# NET.net
KiCad netlist of a schematic drawn in Altium Designer
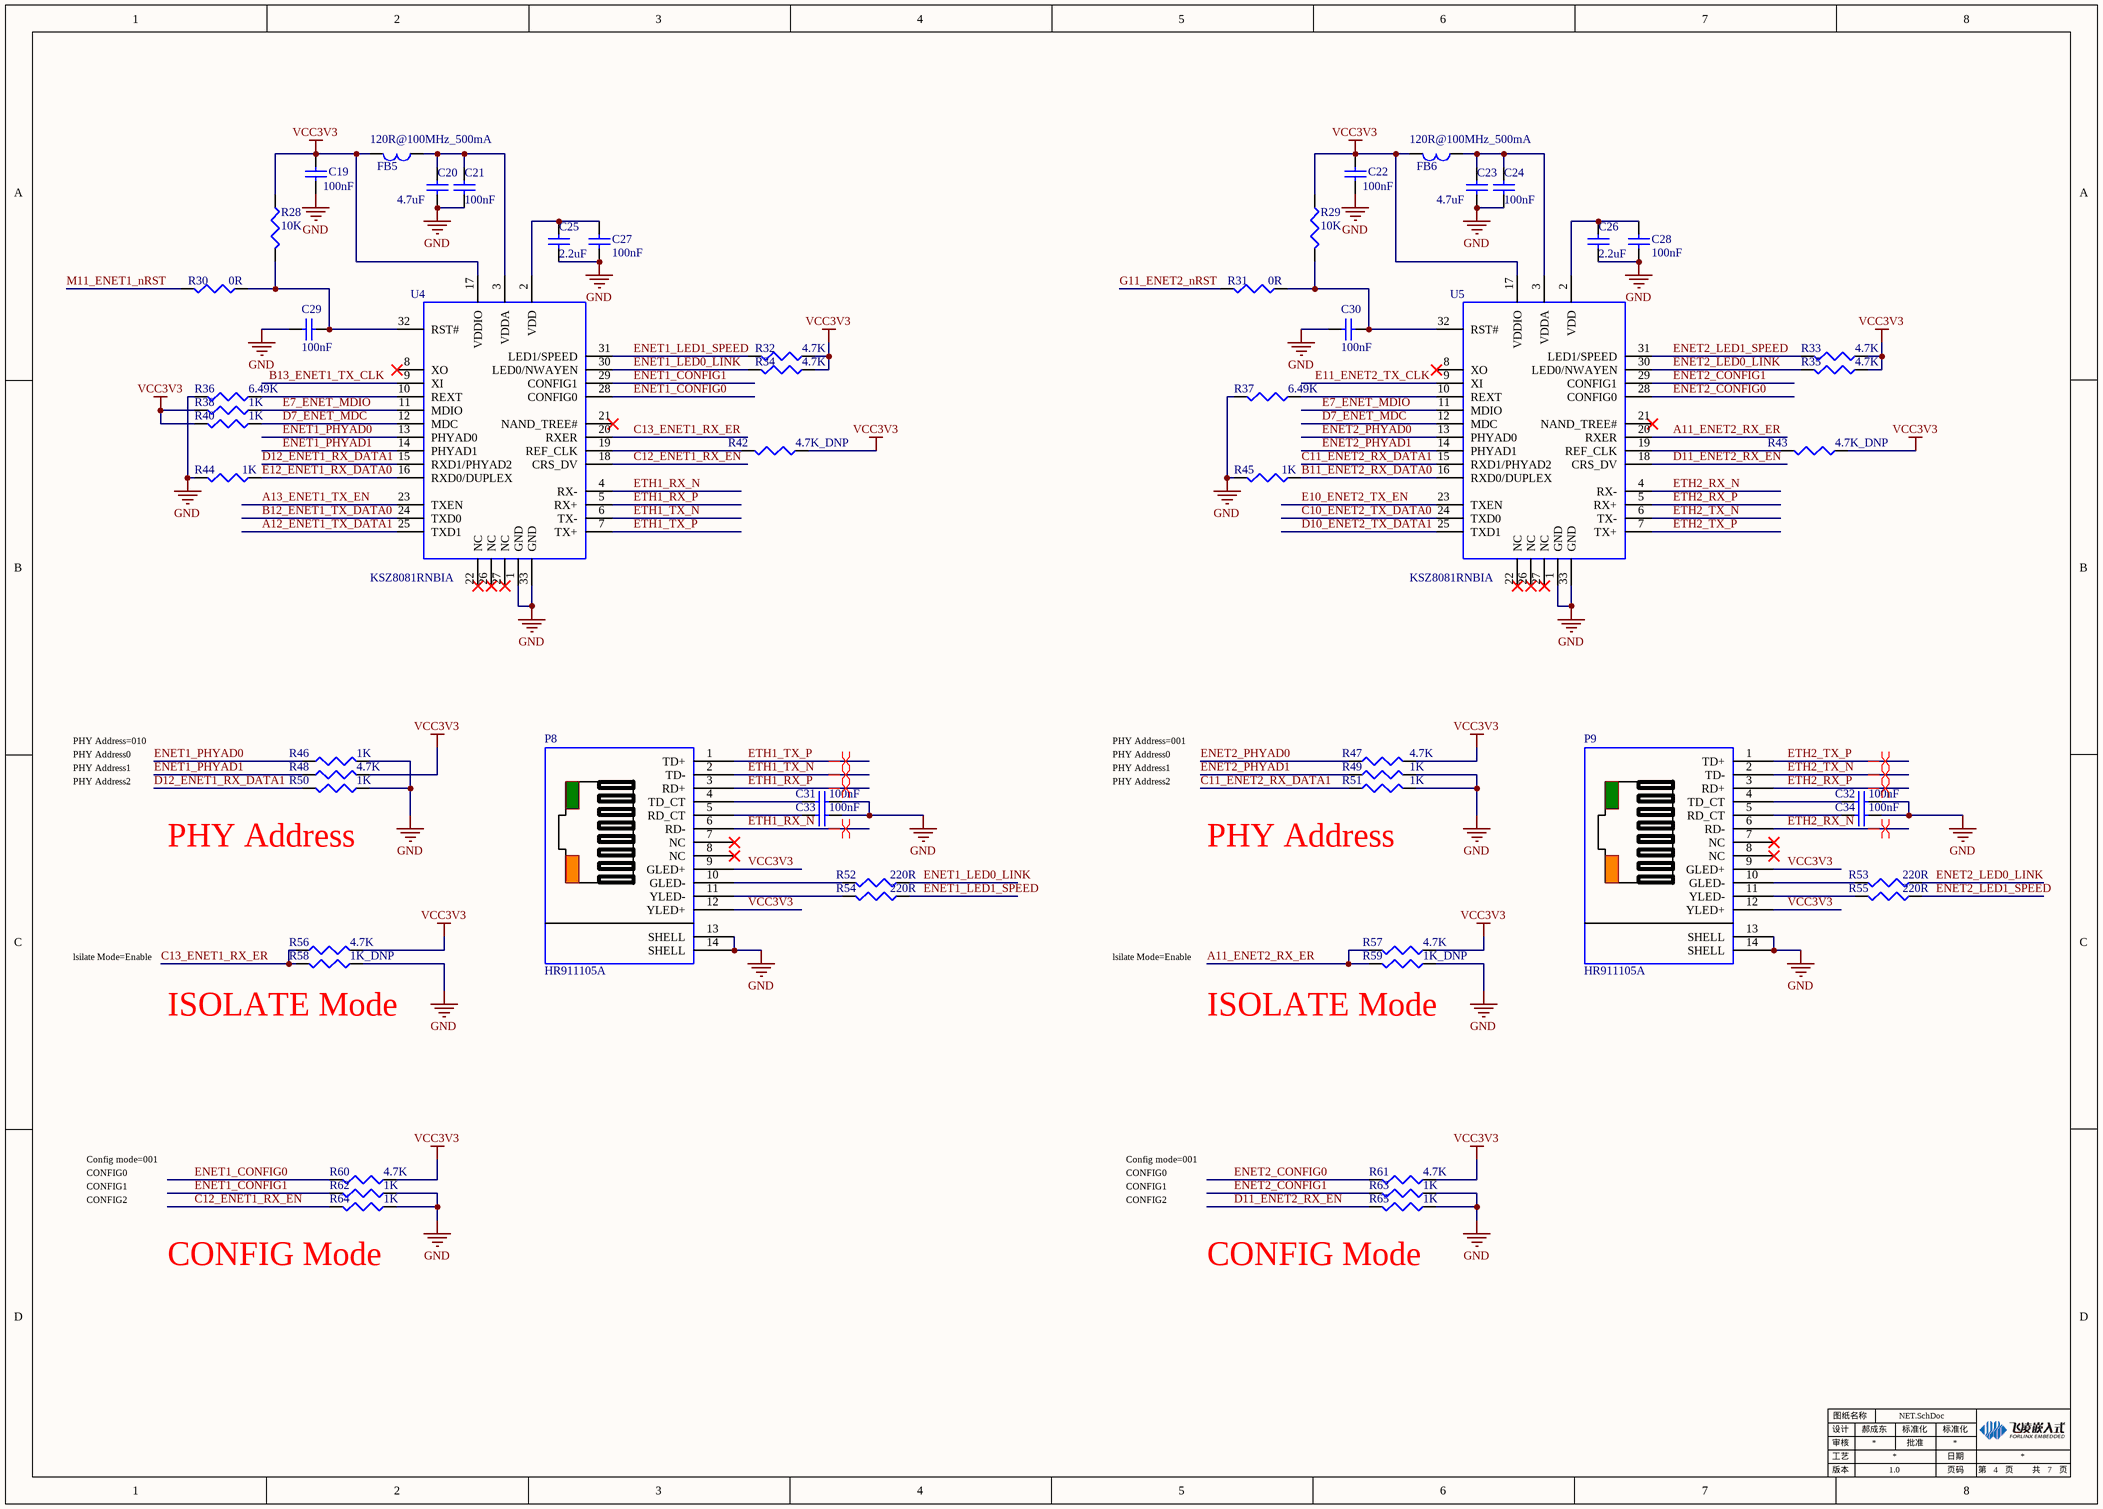
[diagram p0: NET.SchDoc]

(export (version "E")
  (design (tool "Eeschema 10.0.6"))
  (components
    (comp (ref "C19")
      (value "100nF")
      (footprint "0603C+")
      (description "Capacitor")
      (fields (field (name "PUBLISHER") "Altium Limited"))
      (libsource (lib "Miscellaneous Devices") (part "Cap"))
    )
    (comp (ref "C20")
      (value "4.7uF")
      (footprint "0603C+")
      (description "Capacitor")
      (fields (field (name "PUBLISHER") "Altium Limited"))
      (libsource (lib "Miscellaneous Devices") (part "Cap"))
    )
    (comp (ref "C21")
      (value "100nF")
      (footprint "0603C+")
      (description "Capacitor")
      (fields (field (name "PUBLISHER") "Altium Limited"))
      (libsource (lib "Miscellaneous Devices") (part "Cap"))
    )
    (comp (ref "C22")
      (value "100nF")
      (footprint "0603C+")
      (description "Capacitor")
      (fields (field (name "PUBLISHER") "Altium Limited"))
      (libsource (lib "Miscellaneous Devices") (part "Cap"))
    )
    (comp (ref "C23")
      (value "4.7uF")
      (footprint "0603C+")
      (description "Capacitor")
      (fields (field (name "PUBLISHER") "Altium Limited"))
      (libsource (lib "Miscellaneous Devices") (part "Cap"))
    )
    (comp (ref "C24")
      (value "100nF")
      (footprint "0603C+")
      (description "Capacitor")
      (fields (field (name "PUBLISHER") "Altium Limited"))
      (libsource (lib "Miscellaneous Devices") (part "Cap"))
    )
    (comp (ref "C25")
      (value "2.2uF")
      (footprint "0603C+")
      (description "Capacitor")
      (fields (field (name "PUBLISHER") "Altium Limited"))
      (libsource (lib "Miscellaneous Devices") (part "Cap"))
    )
    (comp (ref "C26")
      (value "2.2uF")
      (footprint "0603C+")
      (description "Capacitor")
      (fields (field (name "PUBLISHER") "Altium Limited"))
      (libsource (lib "Miscellaneous Devices") (part "Cap"))
    )
    (comp (ref "C27")
      (value "100nF")
      (footprint "0603C+")
      (description "Capacitor")
      (fields (field (name "PUBLISHER") "Altium Limited"))
      (libsource (lib "Miscellaneous Devices") (part "Cap"))
    )
    (comp (ref "C28")
      (value "100nF")
      (footprint "0603C+")
      (description "Capacitor")
      (fields (field (name "PUBLISHER") "Altium Limited"))
      (libsource (lib "Miscellaneous Devices") (part "Cap"))
    )
    (comp (ref "C29")
      (value "100nF")
      (footprint "0603C+")
      (description "Capacitor")
      (fields (field (name "PUBLISHER") "Altium Limited"))
      (libsource (lib "Miscellaneous Devices") (part "Cap"))
    )
    (comp (ref "C30")
      (value "100nF")
      (footprint "0603C+")
      (description "Capacitor")
      (fields (field (name "PUBLISHER") "Altium Limited"))
      (libsource (lib "Miscellaneous Devices") (part "Cap"))
    )
    (comp (ref "C31")
      (value "100nF")
      (footprint "0603C+")
      (description "Capacitor")
      (fields (field (name "PUBLISHER") "Altium Limited"))
      (libsource (lib "Miscellaneous Devices") (part "Cap"))
    )
    (comp (ref "C32")
      (value "100nF")
      (footprint "0603C+")
      (description "Capacitor")
      (fields (field (name "PUBLISHER") "Altium Limited"))
      (libsource (lib "Miscellaneous Devices") (part "Cap"))
    )
    (comp (ref "C33")
      (value "100nF")
      (footprint "0603C+")
      (description "Capacitor")
      (fields (field (name "PUBLISHER") "Altium Limited"))
      (libsource (lib "Miscellaneous Devices") (part "Cap"))
    )
    (comp (ref "C34")
      (value "100nF")
      (footprint "0603C+")
      (description "Capacitor")
      (fields (field (name "PUBLISHER") "Altium Limited"))
      (libsource (lib "Miscellaneous Devices") (part "Cap"))
    )
    (comp (ref "FB5")
      (value "120R@100MHz_500mA")
      (footprint "0603R+")
      (description "Inductor")
      (fields (field (name "PUBLISHER") "120R@100MHz_500mA"))
      (libsource (lib "Schlib_UL") (part "CZ"))
    )
    (comp (ref "FB6")
      (value "120R@100MHz_500mA")
      (footprint "0603R+")
      (description "Inductor")
      (fields (field (name "PUBLISHER") "120R@100MHz_500mA"))
      (libsource (lib "Schlib_UL") (part "CZ"))
    )
    (comp (ref "P8")
      (value "HR911105A")
      (footprint "RJ-45A12")
      (libsource (lib "PCB_RT1052") (part "HR911105A"))
    )
    (comp (ref "P9")
      (value "HR911105A")
      (footprint "RJ-45A12")
      (libsource (lib "PCB_RT1052") (part "HR911105A"))
    )
    (comp (ref "R28")
      (value "10K")
      (footprint "0603R+")
      (description "Resistor")
      (fields (field (name "PUBLISHER") "Altium Limited"))
      (libsource (lib "Miscellaneous Devices") (part "Res3"))
    )
    (comp (ref "R29")
      (value "10K")
      (footprint "0603R+")
      (description "Resistor")
      (fields (field (name "PUBLISHER") "Altium Limited"))
      (libsource (lib "Miscellaneous Devices") (part "Res3"))
    )
    (comp (ref "R30")
      (value "0R")
      (footprint "0603R+")
      (description "Resistor")
      (fields (field (name "PUBLISHER") "Altium Limited"))
      (libsource (lib "Miscellaneous Devices") (part "Res3"))
    )
    (comp (ref "R31")
      (value "0R")
      (footprint "0603R+")
      (description "Resistor")
      (fields (field (name "PUBLISHER") "Altium Limited"))
      (libsource (lib "Miscellaneous Devices") (part "Res3"))
    )
    (comp (ref "R32")
      (value "4.7K")
      (footprint "0603R+")
      (description "Resistor")
      (fields (field (name "PUBLISHER") "Altium Limited"))
      (libsource (lib "Miscellaneous Devices") (part "Res3"))
    )
    (comp (ref "R33")
      (value "4.7K")
      (footprint "0603R+")
      (description "Resistor")
      (fields (field (name "PUBLISHER") "Altium Limited"))
      (libsource (lib "Miscellaneous Devices") (part "Res3"))
    )
    (comp (ref "R34")
      (value "4.7K")
      (footprint "0603R+")
      (description "Resistor")
      (fields (field (name "PUBLISHER") "Altium Limited"))
      (libsource (lib "Miscellaneous Devices") (part "Res3"))
    )
    (comp (ref "R35")
      (value "4.7K")
      (footprint "0603R+")
      (description "Resistor")
      (fields (field (name "PUBLISHER") "Altium Limited"))
      (libsource (lib "Miscellaneous Devices") (part "Res3"))
    )
    (comp (ref "R36")
      (value "6.49K")
      (footprint "0603R+")
      (description "Resistor")
      (fields (field (name "PUBLISHER") "Altium Limited"))
      (libsource (lib "Miscellaneous Devices") (part "Res3"))
    )
    (comp (ref "R37")
      (value "6.49K")
      (footprint "0603R+")
      (description "Resistor")
      (fields (field (name "PUBLISHER") "Altium Limited"))
      (libsource (lib "Miscellaneous Devices") (part "Res3"))
    )
    (comp (ref "R38")
      (value "1K")
      (footprint "0603R+")
      (description "Resistor")
      (fields (field (name "PUBLISHER") "Altium Limited"))
      (libsource (lib "Miscellaneous Devices") (part "Res3"))
    )
    (comp (ref "R40")
      (value "1K")
      (footprint "0603R+")
      (description "Resistor")
      (fields (field (name "PUBLISHER") "Altium Limited"))
      (libsource (lib "Miscellaneous Devices") (part "Res3"))
    )
    (comp (ref "R42")
      (value "4.7K_DNP")
      (footprint "0603R+")
      (description "Resistor")
      (fields (field (name "PUBLISHER") "Altium Limited"))
      (libsource (lib "Miscellaneous Devices") (part "Res3"))
    )
    (comp (ref "R43")
      (value "4.7K_DNP")
      (footprint "0603R+")
      (description "Resistor")
      (fields (field (name "PUBLISHER") "Altium Limited"))
      (libsource (lib "Miscellaneous Devices") (part "Res3"))
    )
    (comp (ref "R44")
      (value "1K")
      (footprint "0603R+")
      (description "Resistor")
      (fields (field (name "PUBLISHER") "Altium Limited"))
      (libsource (lib "Miscellaneous Devices") (part "Res3"))
    )
    (comp (ref "R45")
      (value "1K")
      (footprint "0603R+")
      (description "Resistor")
      (fields (field (name "PUBLISHER") "Altium Limited"))
      (libsource (lib "Miscellaneous Devices") (part "Res3"))
    )
    (comp (ref "R46")
      (value "1K")
      (footprint "0603R+")
      (description "Resistor")
      (fields (field (name "PUBLISHER") "Altium Limited"))
      (libsource (lib "Miscellaneous Devices") (part "Res3"))
    )
    (comp (ref "R47")
      (value "4.7K")
      (footprint "0603R+")
      (description "Resistor")
      (fields (field (name "PUBLISHER") "Altium Limited"))
      (libsource (lib "Miscellaneous Devices") (part "Res3"))
    )
    (comp (ref "R48")
      (value "4.7K")
      (footprint "0603R+")
      (description "Resistor")
      (fields (field (name "PUBLISHER") "Altium Limited"))
      (libsource (lib "Miscellaneous Devices") (part "Res3"))
    )
    (comp (ref "R49")
      (value "1K")
      (footprint "0603R+")
      (description "Resistor")
      (fields (field (name "PUBLISHER") "Altium Limited"))
      (libsource (lib "Miscellaneous Devices") (part "Res3"))
    )
    (comp (ref "R50")
      (value "1K")
      (footprint "0603R+")
      (description "Resistor")
      (fields (field (name "PUBLISHER") "Altium Limited"))
      (libsource (lib "Miscellaneous Devices") (part "Res3"))
    )
    (comp (ref "R51")
      (value "1K")
      (footprint "0603R+")
      (description "Resistor")
      (fields (field (name "PUBLISHER") "Altium Limited"))
      (libsource (lib "Miscellaneous Devices") (part "Res3"))
    )
    (comp (ref "R52")
      (value "220R")
      (footprint "0603R+")
      (description "Resistor")
      (fields (field (name "PUBLISHER") "Altium Limited"))
      (libsource (lib "Miscellaneous Devices") (part "Res3"))
    )
    (comp (ref "R53")
      (value "220R")
      (footprint "0603R+")
      (description "Resistor")
      (fields (field (name "PUBLISHER") "Altium Limited"))
      (libsource (lib "Miscellaneous Devices") (part "Res3"))
    )
    (comp (ref "R54")
      (value "220R")
      (footprint "0603R+")
      (description "Resistor")
      (fields (field (name "PUBLISHER") "Altium Limited"))
      (libsource (lib "Miscellaneous Devices") (part "Res3"))
    )
    (comp (ref "R55")
      (value "220R")
      (footprint "0603R+")
      (description "Resistor")
      (fields (field (name "PUBLISHER") "Altium Limited"))
      (libsource (lib "Miscellaneous Devices") (part "Res3"))
    )
    (comp (ref "R56")
      (value "4.7K")
      (footprint "0603R+")
      (description "Resistor")
      (fields (field (name "PUBLISHER") "Altium Limited"))
      (libsource (lib "Miscellaneous Devices") (part "Res3"))
    )
    (comp (ref "R57")
      (value "4.7K")
      (footprint "0603R+")
      (description "Resistor")
      (fields (field (name "PUBLISHER") "Altium Limited"))
      (libsource (lib "Miscellaneous Devices") (part "Res3"))
    )
    (comp (ref "R58")
      (value "1K_DNP")
      (footprint "0603R+")
      (description "Resistor")
      (fields (field (name "PUBLISHER") "Altium Limited"))
      (libsource (lib "Miscellaneous Devices") (part "Res3"))
    )
    (comp (ref "R59")
      (value "1K_DNP")
      (footprint "0603R+")
      (description "Resistor")
      (fields (field (name "PUBLISHER") "Altium Limited"))
      (libsource (lib "Miscellaneous Devices") (part "Res3"))
    )
    (comp (ref "R60")
      (value "4.7K")
      (footprint "0603R+")
      (description "Resistor")
      (fields (field (name "PUBLISHER") "Altium Limited"))
      (libsource (lib "Miscellaneous Devices") (part "Res3"))
    )
    (comp (ref "R61")
      (value "4.7K")
      (footprint "0603R+")
      (description "Resistor")
      (fields (field (name "PUBLISHER") "Altium Limited"))
      (libsource (lib "Miscellaneous Devices") (part "Res3"))
    )
    (comp (ref "R62")
      (value "1K")
      (footprint "0603R+")
      (description "Resistor")
      (fields (field (name "PUBLISHER") "Altium Limited"))
      (libsource (lib "Miscellaneous Devices") (part "Res3"))
    )
    (comp (ref "R63")
      (value "1K")
      (footprint "0603R+")
      (description "Resistor")
      (fields (field (name "PUBLISHER") "Altium Limited"))
      (libsource (lib "Miscellaneous Devices") (part "Res3"))
    )
    (comp (ref "R64")
      (value "1K")
      (footprint "0603R+")
      (description "Resistor")
      (fields (field (name "PUBLISHER") "Altium Limited"))
      (libsource (lib "Miscellaneous Devices") (part "Res3"))
    )
    (comp (ref "R65")
      (value "1K")
      (footprint "0603R+")
      (description "Resistor")
      (fields (field (name "PUBLISHER") "Altium Limited"))
      (libsource (lib "Miscellaneous Devices") (part "Res3"))
    )
    (comp (ref "U4")
      (value "KSZ8081RNBIA")
      (footprint "QFN-32")
      (libsource (lib "PCB_RT1052") (part "KSZ8081RNB"))
    )
    (comp (ref "U5")
      (value "KSZ8081RNBIA")
      (footprint "QFN-32")
      (libsource (lib "PCB_RT1052") (part "KSZ8081RNB"))
    )
  )
  (nets
    (net (code "1") (name "/A11_ENET2_RX_ER") (class "Default")
      (node (ref "R57") (pin "2") (pinfunction "2_2") (pintype "passive"))
      (node (ref "R59") (pin "2") (pinfunction "2_2") (pintype "passive"))
      (node (ref "U5") (pin "20") (pinfunction "RXER_20") (pintype "passive"))
    )
    (net (code "2") (name "/A12_ENET1_TX_DATA1") (class "Default")
      (node (ref "U4") (pin "25") (pinfunction "TXD1_25") (pintype "passive"))
    )
    (net (code "3") (name "/A13_ENET1_TX_EN") (class "Default")
      (node (ref "U4") (pin "23") (pinfunction "TXEN_23") (pintype "passive"))
    )
    (net (code "4") (name "/B11_ENET2_RX_DATA0") (class "Default")
      (node (ref "R45") (pin "1") (pinfunction "1_1") (pintype "passive"))
      (node (ref "U5") (pin "16") (pinfunction "RXD0/DUPLEX_16") (pintype "passive"))
    )
    (net (code "5") (name "/B12_ENET1_TX_DATA0") (class "Default")
      (node (ref "U4") (pin "24") (pinfunction "TXD0_24") (pintype "passive"))
    )
    (net (code "6") (name "/B13_ENET1_TX_CLK") (class "Default")
      (node (ref "U4") (pin "9") (pinfunction "XI_9") (pintype "passive"))
    )
    (net (code "7") (name "/C10_ENET2_TX_DATA0") (class "Default")
      (node (ref "U5") (pin "24") (pinfunction "TXD0_24") (pintype "passive"))
    )
    (net (code "8") (name "/C11_ENET2_RX_DATA1") (class "Default")
      (node (ref "R51") (pin "1") (pinfunction "1_1") (pintype "passive"))
      (node (ref "U5") (pin "15") (pinfunction "RXD1/PHYAD2_15") (pintype "passive"))
    )
    (net (code "9") (name "/C12_ENET1_RX_EN") (class "Default")
      (node (ref "R64") (pin "2") (pinfunction "2_2") (pintype "passive"))
      (node (ref "U4") (pin "18") (pinfunction "CRS_DV_18") (pintype "passive"))
    )
    (net (code "10") (name "/C13_ENET1_RX_ER") (class "Default")
      (node (ref "R56") (pin "1") (pinfunction "1_1") (pintype "passive"))
      (node (ref "R58") (pin "2") (pinfunction "2_2") (pintype "passive"))
      (node (ref "U4") (pin "20") (pinfunction "RXER_20") (pintype "passive"))
    )
    (net (code "11") (name "/D7_ENET_MDC") (class "Default")
      (node (ref "R40") (pin "1") (pinfunction "1_1") (pintype "passive"))
      (node (ref "U4") (pin "12") (pinfunction "MDC_12") (pintype "passive"))
      (node (ref "U5") (pin "12") (pinfunction "MDC_12") (pintype "passive"))
    )
    (net (code "12") (name "/D10_ENET2_TX_DATA1") (class "Default")
      (node (ref "U5") (pin "25") (pinfunction "TXD1_25") (pintype "passive"))
    )
    (net (code "13") (name "/D11_ENET2_RX_EN") (class "Default")
      (node (ref "R65") (pin "2") (pinfunction "2_2") (pintype "passive"))
      (node (ref "U5") (pin "18") (pinfunction "CRS_DV_18") (pintype "passive"))
    )
    (net (code "14") (name "/D12_ENET1_RX_DATA1") (class "Default")
      (node (ref "R50") (pin "2") (pinfunction "2_2") (pintype "passive"))
      (node (ref "U4") (pin "15") (pinfunction "RXD1/PHYAD2_15") (pintype "passive"))
    )
    (net (code "15") (name "/E7_ENET_MDIO") (class "Default")
      (node (ref "R38") (pin "1") (pinfunction "1_1") (pintype "passive"))
      (node (ref "U4") (pin "11") (pinfunction "MDIO_11") (pintype "passive"))
      (node (ref "U5") (pin "11") (pinfunction "MDIO_11") (pintype "passive"))
    )
    (net (code "16") (name "/E10_ENET2_TX_EN") (class "Default")
      (node (ref "U5") (pin "23") (pinfunction "TXEN_23") (pintype "passive"))
    )
    (net (code "17") (name "/E11_ENET2_TX_CLK") (class "Default")
      (node (ref "U5") (pin "9") (pinfunction "XI_9") (pintype "passive"))
    )
    (net (code "18") (name "/E12_ENET1_RX_DATA0") (class "Default")
      (node (ref "R44") (pin "1") (pinfunction "1_1") (pintype "passive"))
      (node (ref "U4") (pin "16") (pinfunction "RXD0/DUPLEX_16") (pintype "passive"))
    )
    (net (code "19") (name "/ENET1_CONFIG0") (class "Default")
      (node (ref "R60") (pin "2") (pinfunction "2_2") (pintype "passive"))
      (node (ref "U4") (pin "28") (pinfunction "CONFIG0_28") (pintype "passive"))
    )
    (net (code "20") (name "/ENET1_CONFIG1") (class "Default")
      (node (ref "R62") (pin "2") (pinfunction "2_2") (pintype "passive"))
      (node (ref "U4") (pin "29") (pinfunction "CONFIG1_29") (pintype "passive"))
    )
    (net (code "21") (name "/ENET1_LED0_LINK") (class "Default")
      (node (ref "R34") (pin "2") (pinfunction "2_2") (pintype "passive"))
      (node (ref "R52") (pin "1") (pinfunction "1_1") (pintype "passive"))
      (node (ref "U4") (pin "30") (pinfunction "LED0/NWAYEN_30") (pintype "passive"))
    )
    (net (code "22") (name "/ENET1_LED1_SPEED") (class "Default")
      (node (ref "R32") (pin "2") (pinfunction "2_2") (pintype "passive"))
      (node (ref "R54") (pin "1") (pinfunction "1_1") (pintype "passive"))
      (node (ref "U4") (pin "31") (pinfunction "LED1/SPEED_31") (pintype "passive"))
    )
    (net (code "23") (name "/ENET1_PHYAD0") (class "Default")
      (node (ref "R46") (pin "1") (pinfunction "1_1") (pintype "passive"))
      (node (ref "U4") (pin "13") (pinfunction "PHYAD0_13") (pintype "passive"))
    )
    (net (code "24") (name "/ENET1_PHYAD1") (class "Default")
      (node (ref "R48") (pin "1") (pinfunction "1_1") (pintype "passive"))
      (node (ref "U4") (pin "14") (pinfunction "PHYAD1_14") (pintype "passive"))
    )
    (net (code "25") (name "/ENET2_CONFIG0") (class "Default")
      (node (ref "R61") (pin "2") (pinfunction "2_2") (pintype "passive"))
      (node (ref "U5") (pin "28") (pinfunction "CONFIG0_28") (pintype "passive"))
    )
    (net (code "26") (name "/ENET2_CONFIG1") (class "Default")
      (node (ref "R63") (pin "2") (pinfunction "2_2") (pintype "passive"))
      (node (ref "U5") (pin "29") (pinfunction "CONFIG1_29") (pintype "passive"))
    )
    (net (code "27") (name "/ENET2_LED0_LINK") (class "Default")
      (node (ref "R35") (pin "2") (pinfunction "2_2") (pintype "passive"))
      (node (ref "R53") (pin "1") (pinfunction "1_1") (pintype "passive"))
      (node (ref "U5") (pin "30") (pinfunction "LED0/NWAYEN_30") (pintype "passive"))
    )
    (net (code "28") (name "/ENET2_LED1_SPEED") (class "Default")
      (node (ref "R33") (pin "2") (pinfunction "2_2") (pintype "passive"))
      (node (ref "R55") (pin "1") (pinfunction "1_1") (pintype "passive"))
      (node (ref "U5") (pin "31") (pinfunction "LED1/SPEED_31") (pintype "passive"))
    )
    (net (code "29") (name "/ENET2_PHYAD0") (class "Default")
      (node (ref "R47") (pin "1") (pinfunction "1_1") (pintype "passive"))
      (node (ref "U5") (pin "13") (pinfunction "PHYAD0_13") (pintype "passive"))
    )
    (net (code "30") (name "/ENET2_PHYAD1") (class "Default")
      (node (ref "R49") (pin "1") (pinfunction "1_1") (pintype "passive"))
      (node (ref "U5") (pin "14") (pinfunction "PHYAD1_14") (pintype "passive"))
    )
    (net (code "31") (name "/ETH1_RX_N") (class "Default")
      (node (ref "P8") (pin "6") (pinfunction "RD-_6") (pintype "passive"))
      (node (ref "U4") (pin "4") (pinfunction "RX-_4") (pintype "passive"))
    )
    (net (code "32") (name "/ETH1_RX_P") (class "Default")
      (node (ref "P8") (pin "3") (pinfunction "RD+_3") (pintype "passive"))
      (node (ref "U4") (pin "5") (pinfunction "RX+_5") (pintype "passive"))
    )
    (net (code "33") (name "/ETH1_TX_N") (class "Default")
      (node (ref "P8") (pin "2") (pinfunction "TD-_2") (pintype "passive"))
      (node (ref "U4") (pin "6") (pinfunction "TX-_6") (pintype "passive"))
    )
    (net (code "34") (name "/ETH1_TX_P") (class "Default")
      (node (ref "P8") (pin "1") (pinfunction "TD+_1") (pintype "passive"))
      (node (ref "U4") (pin "7") (pinfunction "TX+_7") (pintype "passive"))
    )
    (net (code "35") (name "/ETH2_RX_N") (class "Default")
      (node (ref "P9") (pin "6") (pinfunction "RD-_6") (pintype "passive"))
      (node (ref "U5") (pin "4") (pinfunction "RX-_4") (pintype "passive"))
    )
    (net (code "36") (name "/ETH2_RX_P") (class "Default")
      (node (ref "P9") (pin "3") (pinfunction "RD+_3") (pintype "passive"))
      (node (ref "U5") (pin "5") (pinfunction "RX+_5") (pintype "passive"))
    )
    (net (code "37") (name "/ETH2_TX_N") (class "Default")
      (node (ref "P9") (pin "2") (pinfunction "TD-_2") (pintype "passive"))
      (node (ref "U5") (pin "6") (pinfunction "TX-_6") (pintype "passive"))
    )
    (net (code "38") (name "/ETH2_TX_P") (class "Default")
      (node (ref "P9") (pin "1") (pinfunction "TD+_1") (pintype "passive"))
      (node (ref "U5") (pin "7") (pinfunction "TX+_7") (pintype "passive"))
    )
    (net (code "39") (name "/G11_ENET2_nRST") (class "Default")
      (node (ref "R31") (pin "2") (pinfunction "2_2") (pintype "passive"))
    )
    (net (code "40") (name "/M11_ENET1_nRST") (class "Default")
      (node (ref "R30") (pin "2") (pinfunction "2_2") (pintype "passive"))
    )
    (net (code "41") (name "GND") (class "Default")
      (node (ref "C19") (pin "2") (pinfunction "2_2") (pintype "passive"))
      (node (ref "C20") (pin "2") (pinfunction "2_2") (pintype "passive"))
      (node (ref "C21") (pin "2") (pinfunction "2_2") (pintype "passive"))
      (node (ref "C22") (pin "2") (pinfunction "2_2") (pintype "passive"))
      (node (ref "C23") (pin "2") (pinfunction "2_2") (pintype "passive"))
      (node (ref "C24") (pin "2") (pinfunction "2_2") (pintype "passive"))
      (node (ref "C25") (pin "2") (pinfunction "2_2") (pintype "passive"))
      (node (ref "C26") (pin "2") (pinfunction "2_2") (pintype "passive"))
      (node (ref "C27") (pin "2") (pinfunction "2_2") (pintype "passive"))
      (node (ref "C28") (pin "2") (pinfunction "2_2") (pintype "passive"))
      (node (ref "C29") (pin "1") (pinfunction "1_1") (pintype "passive"))
      (node (ref "C30") (pin "1") (pinfunction "1_1") (pintype "passive"))
      (node (ref "C31") (pin "1") (pinfunction "1_1") (pintype "passive"))
      (node (ref "C32") (pin "1") (pinfunction "1_1") (pintype "passive"))
      (node (ref "C33") (pin "1") (pinfunction "1_1") (pintype "passive"))
      (node (ref "C34") (pin "1") (pinfunction "1_1") (pintype "passive"))
      (node (ref "P8") (pin "13") (pinfunction "SHELL_13") (pintype "passive"))
      (node (ref "P8") (pin "14") (pinfunction "SHELL_14") (pintype "passive"))
      (node (ref "P9") (pin "13") (pinfunction "SHELL_13") (pintype "passive"))
      (node (ref "P9") (pin "14") (pinfunction "SHELL_14") (pintype "passive"))
      (node (ref "R36") (pin "2") (pinfunction "2_2") (pintype "passive"))
      (node (ref "R37") (pin "2") (pinfunction "2_2") (pintype "passive"))
      (node (ref "R44") (pin "2") (pinfunction "2_2") (pintype "passive"))
      (node (ref "R45") (pin "2") (pinfunction "2_2") (pintype "passive"))
      (node (ref "R46") (pin "2") (pinfunction "2_2") (pintype "passive"))
      (node (ref "R49") (pin "2") (pinfunction "2_2") (pintype "passive"))
      (node (ref "R50") (pin "1") (pinfunction "1_1") (pintype "passive"))
      (node (ref "R51") (pin "2") (pinfunction "2_2") (pintype "passive"))
      (node (ref "R58") (pin "1") (pinfunction "1_1") (pintype "passive"))
      (node (ref "R59") (pin "1") (pinfunction "1_1") (pintype "passive"))
      (node (ref "R62") (pin "1") (pinfunction "1_1") (pintype "passive"))
      (node (ref "R63") (pin "1") (pinfunction "1_1") (pintype "passive"))
      (node (ref "R64") (pin "1") (pinfunction "1_1") (pintype "passive"))
      (node (ref "R65") (pin "1") (pinfunction "1_1") (pintype "passive"))
      (node (ref "U4") (pin "1") (pinfunction "GND_1") (pintype "passive"))
      (node (ref "U4") (pin "33") (pinfunction "GND_33") (pintype "passive"))
      (node (ref "U5") (pin "1") (pinfunction "GND_1") (pintype "passive"))
      (node (ref "U5") (pin "33") (pinfunction "GND_33") (pintype "passive"))
    )
    (net (code "42") (name "Net-(P8-GLED-)") (class "Default")
      (node (ref "P8") (pin "10") (pinfunction "GLED-_10") (pintype "passive"))
      (node (ref "R52") (pin "2") (pinfunction "2_2") (pintype "passive"))
    )
    (net (code "43") (name "Net-(P8-RD_CT)") (class "Default")
      (node (ref "C33") (pin "2") (pinfunction "2_2") (pintype "passive"))
      (node (ref "P8") (pin "5") (pinfunction "RD_CT_5") (pintype "passive"))
    )
    (net (code "44") (name "Net-(P8-TD_CT)") (class "Default")
      (node (ref "C31") (pin "2") (pinfunction "2_2") (pintype "passive"))
      (node (ref "P8") (pin "4") (pinfunction "TD_CT_4") (pintype "passive"))
    )
    (net (code "45") (name "Net-(P8-YLED-)") (class "Default")
      (node (ref "P8") (pin "11") (pinfunction "YLED-_11") (pintype "passive"))
      (node (ref "R54") (pin "2") (pinfunction "2_2") (pintype "passive"))
    )
    (net (code "46") (name "Net-(P9-GLED-)") (class "Default")
      (node (ref "P9") (pin "10") (pinfunction "GLED-_10") (pintype "passive"))
      (node (ref "R53") (pin "2") (pinfunction "2_2") (pintype "passive"))
    )
    (net (code "47") (name "Net-(P9-RD_CT)") (class "Default")
      (node (ref "C34") (pin "2") (pinfunction "2_2") (pintype "passive"))
      (node (ref "P9") (pin "5") (pinfunction "RD_CT_5") (pintype "passive"))
    )
    (net (code "48") (name "Net-(P9-TD_CT)") (class "Default")
      (node (ref "C32") (pin "2") (pinfunction "2_2") (pintype "passive"))
      (node (ref "P9") (pin "4") (pinfunction "TD_CT_4") (pintype "passive"))
    )
    (net (code "49") (name "Net-(P9-YLED-)") (class "Default")
      (node (ref "P9") (pin "11") (pinfunction "YLED-_11") (pintype "passive"))
      (node (ref "R55") (pin "2") (pinfunction "2_2") (pintype "passive"))
    )
    (net (code "50") (name "Net-(U4-REF_CLK)") (class "Default")
      (node (ref "R42") (pin "2") (pinfunction "2_2") (pintype "passive"))
      (node (ref "U4") (pin "19") (pinfunction "REF_CLK_19") (pintype "passive"))
    )
    (net (code "51") (name "Net-(U4-REXT)") (class "Default")
      (node (ref "R36") (pin "1") (pinfunction "1_1") (pintype "passive"))
      (node (ref "U4") (pin "10") (pinfunction "REXT_10") (pintype "passive"))
    )
    (net (code "52") (name "Net-(U4-RST#)") (class "Default")
      (node (ref "C29") (pin "2") (pinfunction "2_2") (pintype "passive"))
      (node (ref "R28") (pin "2") (pinfunction "2_2") (pintype "passive"))
      (node (ref "R30") (pin "1") (pinfunction "1_1") (pintype "passive"))
      (node (ref "U4") (pin "32") (pinfunction "RST#_32") (pintype "passive"))
    )
    (net (code "53") (name "Net-(U4-VDD)") (class "Default")
      (node (ref "C25") (pin "1") (pinfunction "1_1") (pintype "passive"))
      (node (ref "C27") (pin "1") (pinfunction "1_1") (pintype "passive"))
      (node (ref "U4") (pin "2") (pinfunction "VDD_2") (pintype "passive"))
    )
    (net (code "54") (name "Net-(U4-VDDA)") (class "Default")
      (node (ref "C20") (pin "1") (pinfunction "1_1") (pintype "passive"))
      (node (ref "C21") (pin "1") (pinfunction "1_1") (pintype "passive"))
      (node (ref "FB5") (pin "1") (pinfunction "1_1") (pintype "passive"))
      (node (ref "U4") (pin "3") (pinfunction "VDDA_3") (pintype "passive"))
    )
    (net (code "55") (name "Net-(U5-REF_CLK)") (class "Default")
      (node (ref "R43") (pin "2") (pinfunction "2_2") (pintype "passive"))
      (node (ref "U5") (pin "19") (pinfunction "REF_CLK_19") (pintype "passive"))
    )
    (net (code "56") (name "Net-(U5-REXT)") (class "Default")
      (node (ref "R37") (pin "1") (pinfunction "1_1") (pintype "passive"))
      (node (ref "U5") (pin "10") (pinfunction "REXT_10") (pintype "passive"))
    )
    (net (code "57") (name "Net-(U5-RST#)") (class "Default")
      (node (ref "C30") (pin "2") (pinfunction "2_2") (pintype "passive"))
      (node (ref "R29") (pin "2") (pinfunction "2_2") (pintype "passive"))
      (node (ref "R31") (pin "1") (pinfunction "1_1") (pintype "passive"))
      (node (ref "U5") (pin "32") (pinfunction "RST#_32") (pintype "passive"))
    )
    (net (code "58") (name "Net-(U5-VDD)") (class "Default")
      (node (ref "C26") (pin "1") (pinfunction "1_1") (pintype "passive"))
      (node (ref "C28") (pin "1") (pinfunction "1_1") (pintype "passive"))
      (node (ref "U5") (pin "2") (pinfunction "VDD_2") (pintype "passive"))
    )
    (net (code "59") (name "Net-(U5-VDDA)") (class "Default")
      (node (ref "C23") (pin "1") (pinfunction "1_1") (pintype "passive"))
      (node (ref "C24") (pin "1") (pinfunction "1_1") (pintype "passive"))
      (node (ref "FB6") (pin "1") (pinfunction "1_1") (pintype "passive"))
      (node (ref "U5") (pin "3") (pinfunction "VDDA_3") (pintype "passive"))
    )
    (net (code "60") (name "VCC3V3") (class "Default")
      (node (ref "C19") (pin "1") (pinfunction "1_1") (pintype "passive"))
      (node (ref "C22") (pin "1") (pinfunction "1_1") (pintype "passive"))
      (node (ref "FB5") (pin "2") (pinfunction "2_2") (pintype "passive"))
      (node (ref "FB6") (pin "2") (pinfunction "2_2") (pintype "passive"))
      (node (ref "P8") (pin "12") (pinfunction "YLED+_12") (pintype "passive"))
      (node (ref "P8") (pin "9") (pinfunction "GLED+_9") (pintype "passive"))
      (node (ref "P9") (pin "12") (pinfunction "YLED+_12") (pintype "passive"))
      (node (ref "P9") (pin "9") (pinfunction "GLED+_9") (pintype "passive"))
      (node (ref "R28") (pin "1") (pinfunction "1_1") (pintype "passive"))
      (node (ref "R29") (pin "1") (pinfunction "1_1") (pintype "passive"))
      (node (ref "R32") (pin "1") (pinfunction "1_1") (pintype "passive"))
      (node (ref "R33") (pin "1") (pinfunction "1_1") (pintype "passive"))
      (node (ref "R34") (pin "1") (pinfunction "1_1") (pintype "passive"))
      (node (ref "R35") (pin "1") (pinfunction "1_1") (pintype "passive"))
      (node (ref "R38") (pin "2") (pinfunction "2_2") (pintype "passive"))
      (node (ref "R40") (pin "2") (pinfunction "2_2") (pintype "passive"))
      (node (ref "R42") (pin "1") (pinfunction "1_1") (pintype "passive"))
      (node (ref "R43") (pin "1") (pinfunction "1_1") (pintype "passive"))
      (node (ref "R47") (pin "2") (pinfunction "2_2") (pintype "passive"))
      (node (ref "R48") (pin "2") (pinfunction "2_2") (pintype "passive"))
      (node (ref "R56") (pin "2") (pinfunction "2_2") (pintype "passive"))
      (node (ref "R57") (pin "1") (pinfunction "1_1") (pintype "passive"))
      (node (ref "R60") (pin "1") (pinfunction "1_1") (pintype "passive"))
      (node (ref "R61") (pin "1") (pinfunction "1_1") (pintype "passive"))
      (node (ref "U4") (pin "17") (pinfunction "VDDIO_17") (pintype "passive"))
      (node (ref "U5") (pin "17") (pinfunction "VDDIO_17") (pintype "passive"))
    )
    (net (code "61") (name "unconnected-(P8-NC-Pad7)") (class "Default")
      (node (ref "P8") (pin "7") (pinfunction "NC_7") (pintype "passive+no_connect"))
    )
    (net (code "62") (name "unconnected-(P8-NC-Pad8)") (class "Default")
      (node (ref "P8") (pin "8") (pinfunction "NC_8") (pintype "passive+no_connect"))
    )
    (net (code "63") (name "unconnected-(P9-NC-Pad7)") (class "Default")
      (node (ref "P9") (pin "7") (pinfunction "NC_7") (pintype "passive+no_connect"))
    )
    (net (code "64") (name "unconnected-(P9-NC-Pad8)") (class "Default")
      (node (ref "P9") (pin "8") (pinfunction "NC_8") (pintype "passive+no_connect"))
    )
    (net (code "65") (name "unconnected-(U4-NAND_TREE#-Pad21)") (class "Default")
      (node (ref "U4") (pin "21") (pinfunction "NAND_TREE#_21") (pintype "passive+no_connect"))
    )
    (net (code "66") (name "unconnected-(U4-NC-Pad22)") (class "Default")
      (node (ref "U4") (pin "22") (pinfunction "NC_22") (pintype "passive+no_connect"))
    )
    (net (code "67") (name "unconnected-(U4-NC-Pad26)") (class "Default")
      (node (ref "U4") (pin "26") (pinfunction "NC_26") (pintype "passive+no_connect"))
    )
    (net (code "68") (name "unconnected-(U4-NC-Pad27)") (class "Default")
      (node (ref "U4") (pin "27") (pinfunction "NC_27") (pintype "passive+no_connect"))
    )
    (net (code "69") (name "unconnected-(U4-XO-Pad8)") (class "Default")
      (node (ref "U4") (pin "8") (pinfunction "XO_8") (pintype "passive+no_connect"))
    )
    (net (code "70") (name "unconnected-(U5-NAND_TREE#-Pad21)") (class "Default")
      (node (ref "U5") (pin "21") (pinfunction "NAND_TREE#_21") (pintype "passive+no_connect"))
    )
    (net (code "71") (name "unconnected-(U5-NC-Pad22)") (class "Default")
      (node (ref "U5") (pin "22") (pinfunction "NC_22") (pintype "passive+no_connect"))
    )
    (net (code "72") (name "unconnected-(U5-NC-Pad26)") (class "Default")
      (node (ref "U5") (pin "26") (pinfunction "NC_26") (pintype "passive+no_connect"))
    )
    (net (code "73") (name "unconnected-(U5-NC-Pad27)") (class "Default")
      (node (ref "U5") (pin "27") (pinfunction "NC_27") (pintype "passive+no_connect"))
    )
    (net (code "74") (name "unconnected-(U5-XO-Pad8)") (class "Default")
      (node (ref "U5") (pin "8") (pinfunction "XO_8") (pintype "passive+no_connect"))
    )
  )
)
